# iridium.net
KiCad netlist of a schematic drawn in Altium Designer
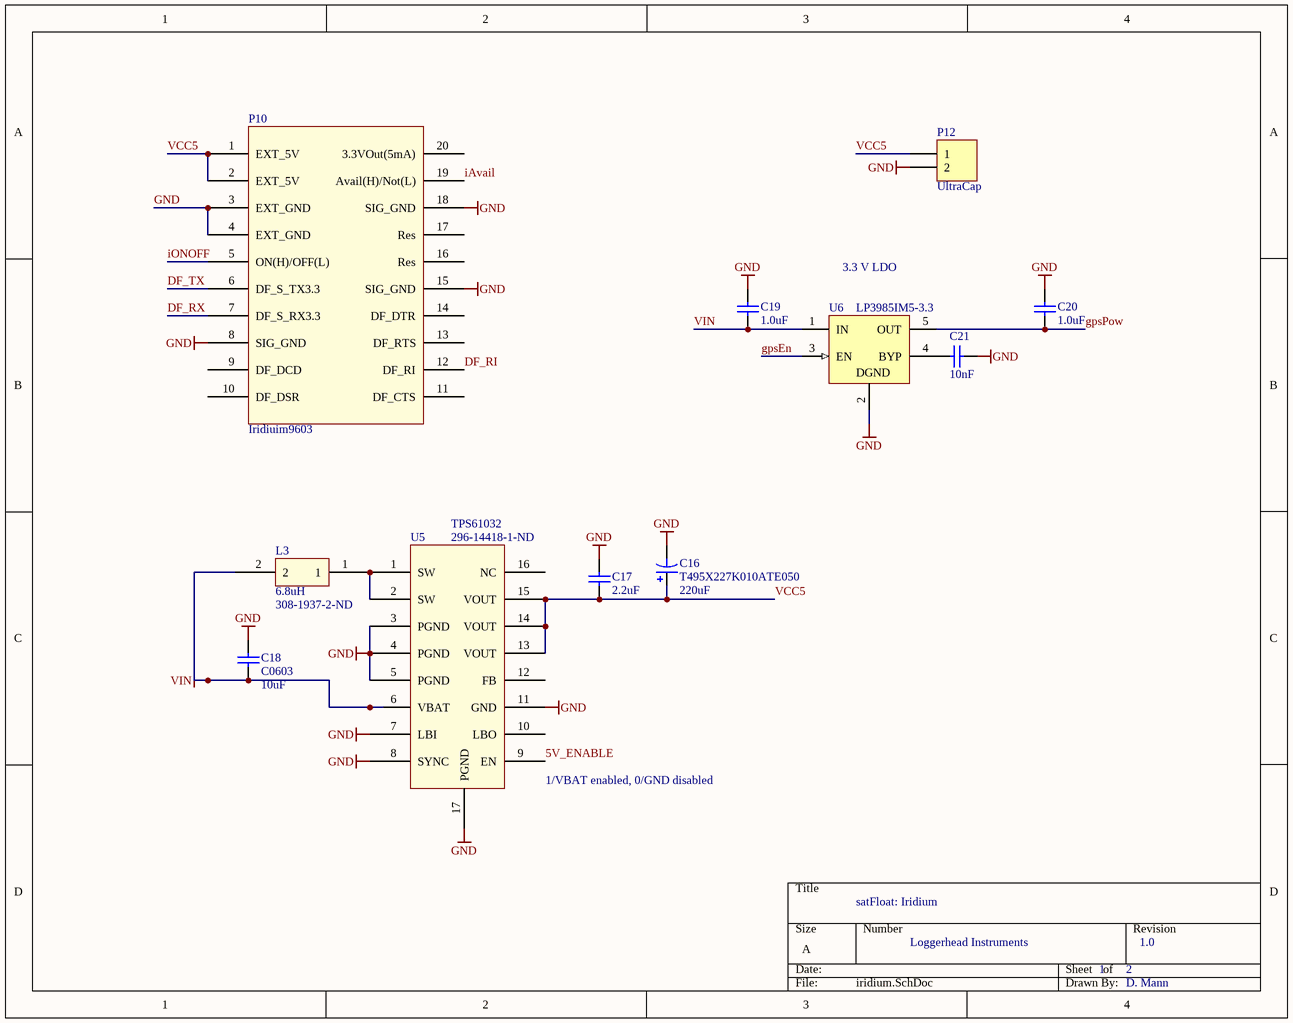
[diagram p0: iridium.SchDoc]

(export (version "E")
  (design (tool "Eeschema 10.0.6"))
  (components
    (comp (ref "C16")
      (value "T495X227K010ATE050")
      (footprint "X")
      (description "Solid Tantalum Chip Capacitor, Standard T495 Series - Low ESR, Surge Robust")
      (fields (field (name "ALTIUM_VALUE") "220uF") (field (name "PUBLISHER") "Altium Limited"))
      (libsource (lib "KEMET Chip Capacitor") (part "T495X"))
    )
    (comp (ref "C17")
      (value "2.2uF")
      (footprint "0402")
      (description "Ceramic Chip Capacitor - Standard")
      (fields (field (name "PUBLISHER") "Altium Limited"))
      (libsource (lib "KEMET Chip Capacitor") (part "C0402"))
    )
    (comp (ref "C18")
      (value "C0603")
      (footprint "0603")
      (description "Ceramic Chip Capacitor - Standard")
      (fields (field (name "ALTIUM_VALUE") "10uF") (field (name "PUBLISHER") "Altium Limited"))
      (libsource (lib "KEMET Chip Capacitor") (part "C0603"))
    )
    (comp (ref "C19")
      (value "1.0uF")
      (footprint "0402")
      (description "Ceramic Chip Capacitor - Standard")
      (fields (field (name "PUBLISHER") "Altium Limited"))
      (libsource (lib "KEMET Chip Capacitor") (part "C0402"))
    )
    (comp (ref "C20")
      (value "1.0uF")
      (footprint "0402")
      (description "Ceramic Chip Capacitor - Standard")
      (fields (field (name "PUBLISHER") "Altium Limited"))
      (libsource (lib "KEMET Chip Capacitor") (part "C0402"))
    )
    (comp (ref "C21")
      (value "10nF")
      (footprint "0402")
      (description "Ceramic Chip Capacitor - Standard")
      (fields (field (name "PUBLISHER") "Altium Limited"))
      (libsource (lib "KEMET Chip Capacitor") (part "C0402"))
    )
    (comp (ref "L3")
      (value "6.8uH")
      (footprint "Inductor - duplicate")
      (description "Sumida Inductor")
      (fields (field (name "SUPPLIER PART NUMBER 1") "308-1937-2-ND"))
      (libsource (lib "Loggerhead") (part "Inductor 6.8uH"))
    )
    (comp (ref "P10")
      (value "Iridiuim9603")
      (footprint "Iridium9603")
      (libsource (lib "Loggerhead") (part "IRIDIUM9603"))
    )
    (comp (ref "P12")
      (value "UltraCap")
      (footprint "HDR1X2")
      (description "Header, 2-Pin")
      (fields (field (name "PUBLISHER") "Altium Limited"))
      (libsource (lib "Miscellaneous Connectors") (part "Header 2"))
    )
    (comp (ref "U5")
      (value "TPS61032")
      (footprint "TPS6103x")
      (description "Boost converter")
      (fields (field (name "SUPPLIER PART NUMBER 2") "296-14418-1-ND"))
      (libsource (lib "Loggerhead") (part "TPS6103x"))
    )
    (comp (ref "U6")
      (value "LP3985IM5-3.3")
      (footprint "MF05A_N")
      (description "Micropower, 150mA Low-Noise Ultra Low-Dropout CMOS Voltage Regulator")
      (fields
        (field (name "MANUFACTURER") "National Semiconductor")
        (field (name "DIGIKEYPARTNUMBER") "LP3985IM5-3.3CT-ND")
        (field (name "PUBLISHER") "Altium Limited")
      )
      (libsource (lib "NSC LDO") (part "LP3985IM5-3.3"))
    )
  )
  (nets
    (net (code "1") (name "/5V_ENABLE") (class "Default")
      (node (ref "U5") (pin "9") (pinfunction "EN_9") (pintype "passive"))
    )
    (net (code "2") (name "/DF_RI") (class "Default")
      (node (ref "P10") (pin "12") (pinfunction "DF_RI_12") (pintype "passive"))
    )
    (net (code "3") (name "/DF_RX") (class "Default")
      (node (ref "P10") (pin "7") (pinfunction "DF_S_RX3.3_7") (pintype "passive"))
    )
    (net (code "4") (name "/DF_TX") (class "Default")
      (node (ref "P10") (pin "6") (pinfunction "DF_S_TX3.3_6") (pintype "passive"))
    )
    (net (code "5") (name "/VCC5") (class "Default")
      (node (ref "C16") (pin "1") (pinfunction "1_1") (pintype "passive"))
      (node (ref "C17") (pin "1") (pinfunction "1_1") (pintype "passive"))
      (node (ref "P10") (pin "1") (pinfunction "EXT_5V_1") (pintype "passive"))
      (node (ref "P10") (pin "2") (pinfunction "EXT_5V_2") (pintype "passive"))
      (node (ref "P12") (pin "1") (pinfunction "1_1") (pintype "passive"))
      (node (ref "U5") (pin "13") (pinfunction "VOUT_13") (pintype "passive"))
      (node (ref "U5") (pin "14") (pinfunction "VOUT_14") (pintype "passive"))
      (node (ref "U5") (pin "15") (pinfunction "VOUT_15") (pintype "passive"))
    )
    (net (code "6") (name "/gpsEn") (class "Default")
      (node (ref "U6") (pin "3") (pinfunction "EN_3") (pintype "input"))
    )
    (net (code "7") (name "/gpsPow") (class "Default")
      (node (ref "C20") (pin "1") (pinfunction "1_1") (pintype "passive"))
      (node (ref "U6") (pin "5") (pinfunction "OUT_5") (pintype "power_in"))
    )
    (net (code "8") (name "/iAvail") (class "Default")
      (node (ref "P10") (pin "19") (pinfunction "Avail(H)/Not(L)_19") (pintype "passive"))
    )
    (net (code "9") (name "/iONOFF") (class "Default")
      (node (ref "P10") (pin "5") (pinfunction "ON(H)/OFF(L)_5") (pintype "passive"))
    )
    (net (code "10") (name "GND") (class "Default")
      (node (ref "C16") (pin "2") (pinfunction "2_2") (pintype "passive"))
      (node (ref "C17") (pin "2") (pinfunction "2_2") (pintype "passive"))
      (node (ref "C18") (pin "1") (pinfunction "1_1") (pintype "passive"))
      (node (ref "C19") (pin "2") (pinfunction "2_2") (pintype "passive"))
      (node (ref "C20") (pin "2") (pinfunction "2_2") (pintype "passive"))
      (node (ref "C21") (pin "1") (pinfunction "1_1") (pintype "passive"))
      (node (ref "P10") (pin "15") (pinfunction "SIG_GND_15") (pintype "passive"))
      (node (ref "P10") (pin "18") (pinfunction "SIG_GND_18") (pintype "passive"))
      (node (ref "P10") (pin "3") (pinfunction "EXT_GND_3") (pintype "passive"))
      (node (ref "P10") (pin "4") (pinfunction "EXT_GND_4") (pintype "passive"))
      (node (ref "P10") (pin "8") (pinfunction "SIG_GND_8") (pintype "passive"))
      (node (ref "P12") (pin "2") (pinfunction "2_2") (pintype "passive"))
      (node (ref "U5") (pin "11") (pinfunction "GND_11") (pintype "passive"))
      (node (ref "U5") (pin "17") (pinfunction "PGND_17") (pintype "passive"))
      (node (ref "U5") (pin "3") (pinfunction "PGND_3") (pintype "passive"))
      (node (ref "U5") (pin "4") (pinfunction "PGND_4") (pintype "passive"))
      (node (ref "U5") (pin "5") (pinfunction "PGND_5") (pintype "passive"))
      (node (ref "U5") (pin "7") (pinfunction "LBI_7") (pintype "passive"))
      (node (ref "U5") (pin "8") (pinfunction "SYNC_8") (pintype "passive"))
      (node (ref "U6") (pin "2") (pinfunction "GND_2") (pintype "power_in"))
    )
    (net (code "11") (name "Net-(L3-Pad1)") (class "Default")
      (node (ref "L3") (pin "1") (pinfunction "1_1") (pintype "passive"))
      (node (ref "U5") (pin "1") (pinfunction "SW_1") (pintype "passive"))
      (node (ref "U5") (pin "2") (pinfunction "SW_2") (pintype "passive"))
    )
    (net (code "12") (name "Net-(U6-BYP)") (class "Default")
      (node (ref "C21") (pin "2") (pinfunction "2_2") (pintype "passive"))
      (node (ref "U6") (pin "4") (pinfunction "BYP_4") (pintype "passive"))
    )
    (net (code "13") (name "VIN") (class "Default")
      (node (ref "C18") (pin "2") (pinfunction "2_2") (pintype "passive"))
      (node (ref "C19") (pin "1") (pinfunction "1_1") (pintype "passive"))
      (node (ref "L3") (pin "2") (pinfunction "2_2") (pintype "passive"))
      (node (ref "U5") (pin "6") (pinfunction "VBAT_6") (pintype "passive"))
      (node (ref "U6") (pin "1") (pinfunction "IN_1") (pintype "power_in"))
    )
    (net (code "14") (name "unconnected-(P10-3.3VOut(5mA)-Pad20)") (class "Default")
      (node (ref "P10") (pin "20") (pinfunction "3.3VOut(5mA)_20") (pintype "passive"))
    )
    (net (code "15") (name "unconnected-(P10-DF_CTS-Pad11)") (class "Default")
      (node (ref "P10") (pin "11") (pinfunction "DF_CTS_11") (pintype "passive"))
    )
    (net (code "16") (name "unconnected-(P10-DF_DCD-Pad9)") (class "Default")
      (node (ref "P10") (pin "9") (pinfunction "DF_DCD_9") (pintype "passive"))
    )
    (net (code "17") (name "unconnected-(P10-DF_DSR-Pad10)") (class "Default")
      (node (ref "P10") (pin "10") (pinfunction "DF_DSR_10") (pintype "passive"))
    )
    (net (code "18") (name "unconnected-(P10-DF_DTR-Pad14)") (class "Default")
      (node (ref "P10") (pin "14") (pinfunction "DF_DTR_14") (pintype "passive"))
    )
    (net (code "19") (name "unconnected-(P10-DF_RTS-Pad13)") (class "Default")
      (node (ref "P10") (pin "13") (pinfunction "DF_RTS_13") (pintype "passive"))
    )
    (net (code "20") (name "unconnected-(P10-Res-Pad16)") (class "Default")
      (node (ref "P10") (pin "16") (pinfunction "Res_16") (pintype "passive"))
    )
    (net (code "21") (name "unconnected-(P10-Res-Pad17)") (class "Default")
      (node (ref "P10") (pin "17") (pinfunction "Res_17") (pintype "passive"))
    )
    (net (code "22") (name "unconnected-(U5-FB-Pad12)") (class "Default")
      (node (ref "U5") (pin "12") (pinfunction "FB_12") (pintype "passive"))
    )
    (net (code "23") (name "unconnected-(U5-LBO-Pad10)") (class "Default")
      (node (ref "U5") (pin "10") (pinfunction "LBO_10") (pintype "passive"))
    )
    (net (code "24") (name "unconnected-(U5-NC-Pad16)") (class "Default")
      (node (ref "U5") (pin "16") (pinfunction "NC_16") (pintype "passive"))
    )
  )
)
